# DuinoTag.net
KiCad netlist of a schematic drawn in Altium Designer
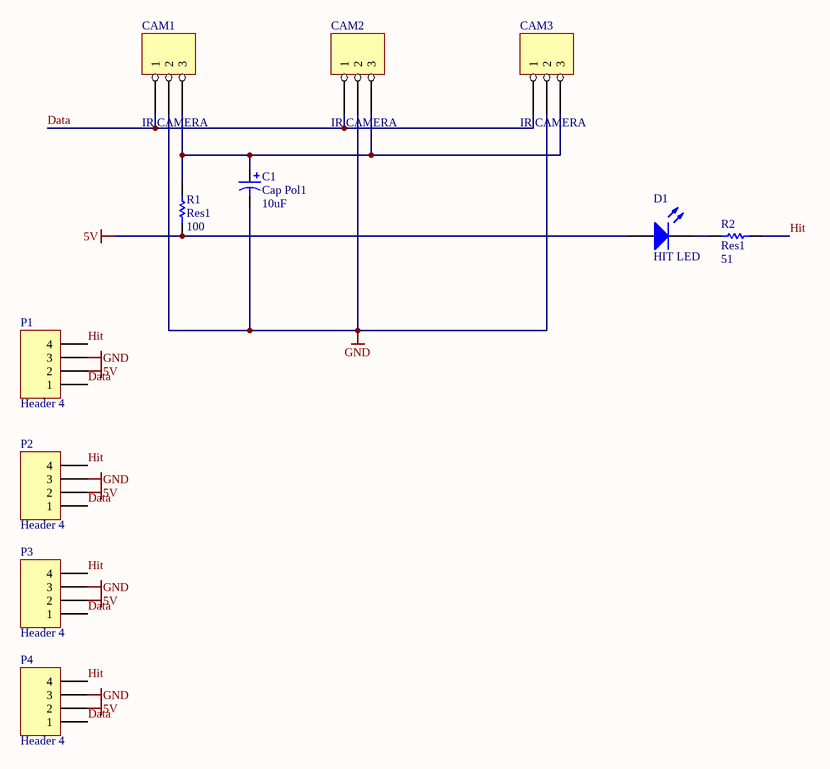
[diagram p0: DuinoTag.SchDoc]

(export (version "E")
  (design (tool "Eeschema 10.0.6"))
  (components
    (comp (ref "C1")
      (value "Cap Pol1")
      (footprint "Vishay Footprints:94SP-C")
      (description "Polarized Capacitor (Radial)")
      (fields (field (name "ALTIUM_VALUE") "10uF") (field (name "PUBLISHER") "Altium Limited"))
      (libsource (lib "Miscellaneous Devices") (part "Cap Pol1"))
    )
    (comp (ref "CAM1")
      (value "IR CAMERA")
      (footprint "SIP3")
      (description "CONN HEADR BRKWAY .100 3POS STR")
      (libsource (lib "raven-parts") (part "HEADER 3"))
    )
    (comp (ref "CAM2")
      (value "IR CAMERA")
      (footprint "SIP3")
      (description "CONN HEADR BRKWAY .100 3POS STR")
      (libsource (lib "raven-parts") (part "HEADER 3"))
    )
    (comp (ref "CAM3")
      (value "IR CAMERA")
      (footprint "SIP3")
      (description "CONN HEADR BRKWAY .100 3POS STR")
      (libsource (lib "raven-parts") (part "HEADER 3"))
    )
    (comp (ref "D1")
      (value "HIT LED")
      (footprint "LED-1")
      (description "Typical RED GaAs LED")
      (fields (field (name "PUBLISHER") "Altium Limited"))
      (libsource (lib "Miscellaneous Devices") (part "LED1"))
    )
    (comp (ref "P1")
      (value "Header 4")
      (footprint "HDR1X4")
      (description "Header, 4-Pin")
      (fields (field (name "PUBLISHER") "Altium Limited"))
      (libsource (lib "Miscellaneous Connectors") (part "Header 4"))
    )
    (comp (ref "P2")
      (value "Header 4")
      (footprint "HDR1X4")
      (description "Header, 4-Pin")
      (fields (field (name "PUBLISHER") "Altium Limited"))
      (libsource (lib "Miscellaneous Connectors") (part "Header 4"))
    )
    (comp (ref "P3")
      (value "Header 4")
      (footprint "HDR1X4")
      (description "Header, 4-Pin")
      (fields (field (name "PUBLISHER") "Altium Limited"))
      (libsource (lib "Miscellaneous Connectors") (part "Header 4"))
    )
    (comp (ref "P4")
      (value "Header 4")
      (footprint "HDR1X4")
      (description "Header, 4-Pin")
      (fields (field (name "PUBLISHER") "Altium Limited"))
      (libsource (lib "Miscellaneous Connectors") (part "Header 4"))
    )
    (comp (ref "R1")
      (value "Res1")
      (footprint "AXIAL-0.3")
      (description "Resistor")
      (fields (field (name "ALTIUM_VALUE") "100") (field (name "PUBLISHER") "Altium Limited"))
      (libsource (lib "Miscellaneous Devices") (part "Res1"))
    )
    (comp (ref "R2")
      (value "Res1")
      (footprint "AXIAL-0.3")
      (description "Resistor")
      (fields (field (name "ALTIUM_VALUE") "51") (field (name "PUBLISHER") "Altium Limited"))
      (libsource (lib "Miscellaneous Devices") (part "Res1"))
    )
  )
  (nets
    (net (code "1") (name "/Data") (class "Default")
      (node (ref "CAM1") (pin "1") (pinfunction "1_1") (pintype "passive"))
      (node (ref "CAM2") (pin "1") (pinfunction "1_1") (pintype "passive"))
      (node (ref "CAM3") (pin "1") (pinfunction "1_1") (pintype "passive"))
      (node (ref "P1") (pin "1") (pinfunction "1_1") (pintype "passive"))
      (node (ref "P2") (pin "1") (pinfunction "1_1") (pintype "passive"))
      (node (ref "P3") (pin "1") (pinfunction "1_1") (pintype "passive"))
      (node (ref "P4") (pin "1") (pinfunction "1_1") (pintype "passive"))
    )
    (net (code "2") (name "/Hit") (class "Default")
      (node (ref "P1") (pin "4") (pinfunction "4_4") (pintype "passive"))
      (node (ref "P2") (pin "4") (pinfunction "4_4") (pintype "passive"))
      (node (ref "P3") (pin "4") (pinfunction "4_4") (pintype "passive"))
      (node (ref "P4") (pin "4") (pinfunction "4_4") (pintype "passive"))
      (node (ref "R2") (pin "1") (pinfunction "1_1") (pintype "passive"))
    )
    (net (code "3") (name "5V") (class "Default")
      (node (ref "D1") (pin "1") (pinfunction "A_1") (pintype "passive"))
      (node (ref "P1") (pin "2") (pinfunction "2_2") (pintype "passive"))
      (node (ref "P2") (pin "2") (pinfunction "2_2") (pintype "passive"))
      (node (ref "P3") (pin "2") (pinfunction "2_2") (pintype "passive"))
      (node (ref "P4") (pin "2") (pinfunction "2_2") (pintype "passive"))
      (node (ref "R1") (pin "1") (pinfunction "1_1") (pintype "passive"))
    )
    (net (code "4") (name "GND") (class "Default")
      (node (ref "C1") (pin "2") (pinfunction "2_2") (pintype "passive"))
      (node (ref "CAM1") (pin "2") (pinfunction "2_2") (pintype "passive"))
      (node (ref "CAM2") (pin "2") (pinfunction "2_2") (pintype "passive"))
      (node (ref "CAM3") (pin "2") (pinfunction "2_2") (pintype "passive"))
      (node (ref "P1") (pin "3") (pinfunction "3_3") (pintype "passive"))
      (node (ref "P2") (pin "3") (pinfunction "3_3") (pintype "passive"))
      (node (ref "P3") (pin "3") (pinfunction "3_3") (pintype "passive"))
      (node (ref "P4") (pin "3") (pinfunction "3_3") (pintype "passive"))
    )
    (net (code "5") (name "Net-(C1-Pad1)") (class "Default")
      (node (ref "C1") (pin "1") (pinfunction "1_1") (pintype "passive"))
      (node (ref "CAM1") (pin "3") (pinfunction "3_3") (pintype "passive"))
      (node (ref "CAM2") (pin "3") (pinfunction "3_3") (pintype "passive"))
      (node (ref "CAM3") (pin "3") (pinfunction "3_3") (pintype "passive"))
      (node (ref "R1") (pin "2") (pinfunction "2_2") (pintype "passive"))
    )
    (net (code "6") (name "Net-(D1-K)") (class "Default")
      (node (ref "D1") (pin "2") (pinfunction "K_2") (pintype "passive"))
      (node (ref "R2") (pin "2") (pinfunction "2_2") (pintype "passive"))
    )
  )
)
